# BC127.net
KiCad netlist of a schematic drawn in Altium Designer
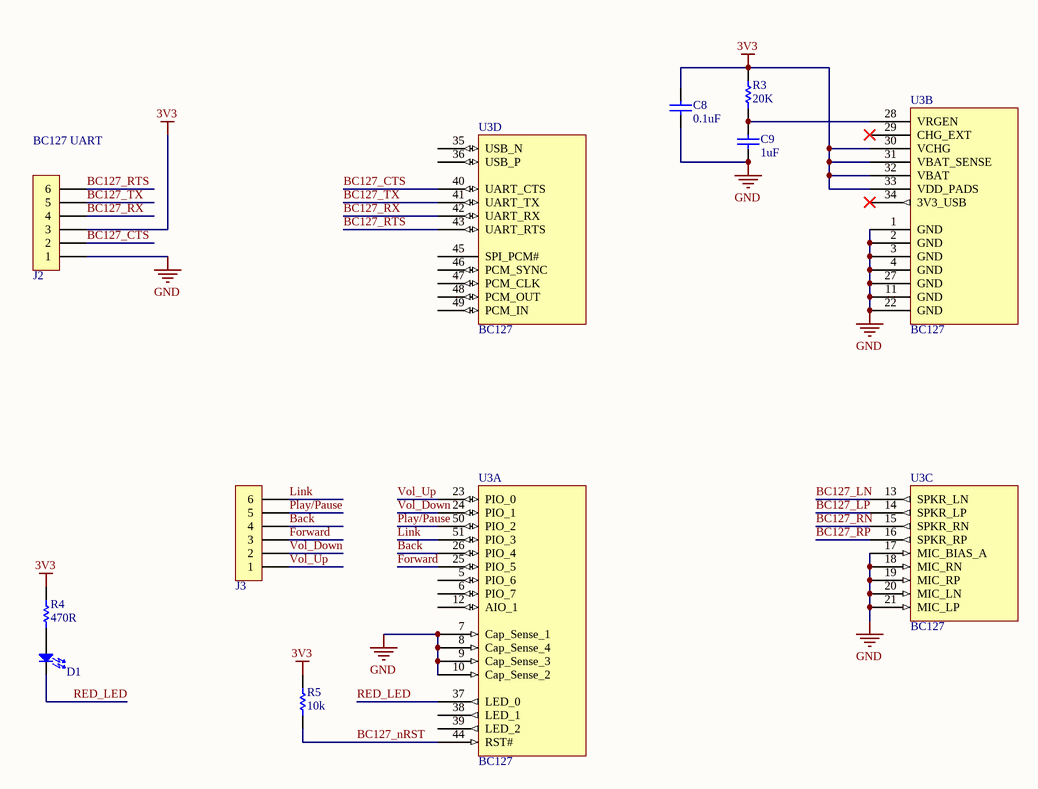
[diagram p0: BC127.SchDoc]

(export (version "E")
  (design (tool "Eeschema 10.0.6"))
  (components
    (comp (ref "C8")
      (value "0.1uF")
      (footprint "CAPC1608X09N")
      (fields
        (field (name "DIGIKEY PART NUMBER") "490-1519-1-ND")
        (field (name "VOLTAGE") "50V")
        (field (name "TOLERANCE") "10%")
      )
      (libsource (lib "Speaker Library") (part "CAP CER 0.1uF 0603"))
    )
    (comp (ref "C9")
      (value "1uF")
      (footprint "CAPC1608X09N")
      (fields
        (field (name "DIGIKEY PART NUMBER") "490-10487-1-ND")
        (field (name "VOLTAGE") "35V")
        (field (name "MANUFACTURER") "Murata")
      )
      (libsource (lib "Speaker Library") (part "CAP CER 1uF 0603"))
    )
    (comp (ref "D1")
      (value "LED 0603")
      (footprint "DIOM1608X08N")
      (fields (field (name "VOLTAGE") "2.2V") (field (name "DIGIKEY PART NUMBER") "160-1447-1-ND"))
      (libsource (lib "Speaker Library") (part "LED 0603"))
    )
    (comp (ref "J2")
      (value "6POS THRU HOLE 2.0MM")
      (footprint "JST PH-6")
      (fields (field (name "DIGIKEY PART NUMBER") "455-1708-ND"))
      (libsource (lib "Speaker Library") (part "6POS THRU HOLE 2.0MM"))
    )
    (comp (ref "J3")
      (value "6POS THRU HOLE 2.0MM")
      (footprint "JST PH-6")
      (fields (field (name "DIGIKEY PART NUMBER") "455-1708-ND"))
      (libsource (lib "Speaker Library") (part "6POS THRU HOLE 2.0MM"))
    )
    (comp (ref "R3")
      (value "20K")
      (footprint "RESC1608X06N")
      (fields
        (field (name "TOLERANCE") "1%")
        (field (name "POWER") "0.1W")
        (field (name "DIGIKEY PART NUMBER") "311-20.0KHRCT-ND")
      )
      (libsource (lib "Speaker Library") (part "RES 20K 0603"))
    )
    (comp (ref "R4")
      (value "470R")
      (footprint "RESC1608X06N")
      (fields
        (field (name "TOLERANCE") "1%")
        (field (name "POWER") "0.25W")
        (field (name "DIGIKEY PART NUMBER") "311-470HRCT-ND")
      )
      (libsource (lib "Speaker Library") (part "RES 470R 0603"))
    )
    (comp (ref "R5")
      (value "10k")
      (footprint "RESC1608X06N")
      (fields
        (field (name "TOLERANCE") "1%")
        (field (name "POWER") "0.1W")
        (field (name "MANUFACTURER") "Yageo")
      )
      (libsource (lib "Speaker Library") (part "RES 10K 0603"))
    )
    (comp (ref "U3") (value "BC127") (footprint "BC127") (libsource (lib "Speaker Library") (part "BC127")))
  )
  (nets
    (net (code "1") (name "/BC127_CTS") (class "Default")
      (node (ref "J2") (pin "2") (pinfunction "2_2") (pintype "passive"))
      (node (ref "U3") (pin "40") (pinfunction "UART_CTS_40") (pintype "bidirectional"))
    )
    (net (code "2") (name "/BC127_LN") (class "Default")
      (node (ref "U3") (pin "13") (pinfunction "SPKR_LN_13") (pintype "output"))
    )
    (net (code "3") (name "/BC127_LP") (class "Default")
      (node (ref "U3") (pin "14") (pinfunction "SPKR_LP_14") (pintype "output"))
    )
    (net (code "4") (name "/BC127_RN") (class "Default")
      (node (ref "U3") (pin "15") (pinfunction "SPKR_RN_15") (pintype "output"))
    )
    (net (code "5") (name "/BC127_RP") (class "Default")
      (node (ref "U3") (pin "16") (pinfunction "SPKR_RP_16") (pintype "output"))
    )
    (net (code "6") (name "/BC127_RTS") (class "Default")
      (node (ref "J2") (pin "6") (pinfunction "6_6") (pintype "passive"))
      (node (ref "U3") (pin "43") (pinfunction "UART_RTS_43") (pintype "bidirectional"))
    )
    (net (code "7") (name "/BC127_RX") (class "Default")
      (node (ref "J2") (pin "4") (pinfunction "4_4") (pintype "passive"))
      (node (ref "U3") (pin "42") (pinfunction "UART_RX_42") (pintype "bidirectional"))
    )
    (net (code "8") (name "/BC127_TX") (class "Default")
      (node (ref "J2") (pin "5") (pinfunction "5_5") (pintype "passive"))
      (node (ref "U3") (pin "41") (pinfunction "UART_TX_41") (pintype "bidirectional"))
    )
    (net (code "9") (name "/BC127_nRST") (class "Default")
      (node (ref "R5") (pin "1") (pinfunction "1_1") (pintype "passive"))
      (node (ref "U3") (pin "44") (pinfunction "RST#_44") (pintype "input"))
    )
    (net (code "10") (name "/Back") (class "Default")
      (node (ref "J3") (pin "4") (pinfunction "4_4") (pintype "passive"))
      (node (ref "U3") (pin "26") (pinfunction "PIO_4_26") (pintype "bidirectional"))
    )
    (net (code "11") (name "/Forward") (class "Default")
      (node (ref "J3") (pin "3") (pinfunction "3_3") (pintype "passive"))
      (node (ref "U3") (pin "25") (pinfunction "PIO_5_25") (pintype "bidirectional"))
    )
    (net (code "12") (name "/Link") (class "Default")
      (node (ref "J3") (pin "6") (pinfunction "6_6") (pintype "passive"))
      (node (ref "U3") (pin "51") (pinfunction "PIO_3_51") (pintype "bidirectional"))
    )
    (net (code "13") (name "/Play{slash}Pause") (class "Default")
      (node (ref "J3") (pin "5") (pinfunction "5_5") (pintype "passive"))
      (node (ref "U3") (pin "50") (pinfunction "PIO_2_50") (pintype "bidirectional"))
    )
    (net (code "14") (name "/RED_LED") (class "Default")
      (node (ref "D1") (pin "1") (pinfunction "K2_1") (pintype "passive"))
      (node (ref "U3") (pin "37") (pinfunction "LED_0_37") (pintype "output"))
    )
    (net (code "15") (name "/Vol_Down") (class "Default")
      (node (ref "J3") (pin "2") (pinfunction "2_2") (pintype "passive"))
      (node (ref "U3") (pin "24") (pinfunction "PIO_1_24") (pintype "bidirectional"))
    )
    (net (code "16") (name "/Vol_Up") (class "Default")
      (node (ref "J3") (pin "1") (pinfunction "1_1") (pintype "passive"))
      (node (ref "U3") (pin "23") (pinfunction "PIO_0_23") (pintype "bidirectional"))
    )
    (net (code "17") (name "3V3") (class "Default")
      (node (ref "C8") (pin "2") (pinfunction "2_2") (pintype "passive"))
      (node (ref "J2") (pin "3") (pinfunction "3_3") (pintype "passive"))
      (node (ref "R3") (pin "2") (pinfunction "2_2") (pintype "passive"))
      (node (ref "R4") (pin "2") (pinfunction "2_2") (pintype "passive"))
      (node (ref "R5") (pin "2") (pinfunction "2_2") (pintype "passive"))
      (node (ref "U3") (pin "30") (pinfunction "VCHG_30") (pintype "passive"))
      (node (ref "U3") (pin "31") (pinfunction "VBAT_SENSE_31") (pintype "passive"))
      (node (ref "U3") (pin "32") (pinfunction "VBAT_32") (pintype "passive"))
      (node (ref "U3") (pin "33") (pinfunction "VDD_PADS_33") (pintype "power_in"))
    )
    (net (code "18") (name "GND") (class "Default")
      (node (ref "C8") (pin "1") (pinfunction "1_1") (pintype "passive"))
      (node (ref "C9") (pin "1") (pinfunction "1_1") (pintype "passive"))
      (node (ref "J2") (pin "1") (pinfunction "1_1") (pintype "passive"))
      (node (ref "U3") (pin "1") (pinfunction "GND_1") (pintype "power_in"))
      (node (ref "U3") (pin "10") (pinfunction "Cap_Sense_2_10") (pintype "input"))
      (node (ref "U3") (pin "11") (pinfunction "GND_11") (pintype "power_in"))
      (node (ref "U3") (pin "17") (pinfunction "MIC_BIAS_A_17") (pintype "input"))
      (node (ref "U3") (pin "18") (pinfunction "MIC_RN_18") (pintype "input"))
      (node (ref "U3") (pin "19") (pinfunction "MIC_RP_19") (pintype "input"))
      (node (ref "U3") (pin "2") (pinfunction "GND_2") (pintype "power_in"))
      (node (ref "U3") (pin "20") (pinfunction "MIC_LN_20") (pintype "input"))
      (node (ref "U3") (pin "21") (pinfunction "MIC_LP_21") (pintype "input"))
      (node (ref "U3") (pin "22") (pinfunction "GND_22") (pintype "power_in"))
      (node (ref "U3") (pin "27") (pinfunction "GND_27") (pintype "power_in"))
      (node (ref "U3") (pin "3") (pinfunction "GND_3") (pintype "power_in"))
      (node (ref "U3") (pin "4") (pinfunction "GND_4") (pintype "power_in"))
      (node (ref "U3") (pin "7") (pinfunction "Cap_Sense_1_7") (pintype "input"))
      (node (ref "U3") (pin "8") (pinfunction "Cap_Sense_4_8") (pintype "input"))
      (node (ref "U3") (pin "9") (pinfunction "Cap_Sense_3_9") (pintype "input"))
    )
    (net (code "19") (name "Net-(D1-A2)") (class "Default")
      (node (ref "D1") (pin "2") (pinfunction "A2_2") (pintype "passive"))
      (node (ref "R4") (pin "1") (pinfunction "1_1") (pintype "passive"))
    )
    (net (code "20") (name "Net-(U3B-VRGEN)") (class "Default")
      (node (ref "C9") (pin "2") (pinfunction "2_2") (pintype "passive"))
      (node (ref "R3") (pin "1") (pinfunction "1_1") (pintype "passive"))
      (node (ref "U3") (pin "28") (pinfunction "VRGEN_28") (pintype "passive"))
    )
    (net (code "21") (name "unconnected-(U3A-AIO_1-Pad12)") (class "Default")
      (node (ref "U3") (pin "12") (pinfunction "AIO_1_12") (pintype "bidirectional"))
    )
    (net (code "22") (name "unconnected-(U3A-LED_1-Pad38)") (class "Default")
      (node (ref "U3") (pin "38") (pinfunction "LED_1_38") (pintype "output"))
    )
    (net (code "23") (name "unconnected-(U3A-LED_2-Pad39)") (class "Default")
      (node (ref "U3") (pin "39") (pinfunction "LED_2_39") (pintype "output"))
    )
    (net (code "24") (name "unconnected-(U3A-PIO_6-Pad5)") (class "Default")
      (node (ref "U3") (pin "5") (pinfunction "PIO_6_5") (pintype "bidirectional"))
    )
    (net (code "25") (name "unconnected-(U3A-PIO_7-Pad6)") (class "Default")
      (node (ref "U3") (pin "6") (pinfunction "PIO_7_6") (pintype "bidirectional"))
    )
    (net (code "26") (name "unconnected-(U3B-3V3_USB-Pad34)") (class "Default")
      (node (ref "U3") (pin "34") (pinfunction "3V3_USB_34") (pintype "output+no_connect"))
    )
    (net (code "27") (name "unconnected-(U3B-CHG_EXT-Pad29)") (class "Default")
      (node (ref "U3") (pin "29") (pinfunction "CHG_EXT_29") (pintype "passive+no_connect"))
    )
    (net (code "28") (name "unconnected-(U3D-PCM_CLK-Pad47)") (class "Default")
      (node (ref "U3") (pin "47") (pinfunction "PCM_CLK_47") (pintype "bidirectional"))
    )
    (net (code "29") (name "unconnected-(U3D-PCM_IN-Pad49)") (class "Default")
      (node (ref "U3") (pin "49") (pinfunction "PCM_IN_49") (pintype "bidirectional"))
    )
    (net (code "30") (name "unconnected-(U3D-PCM_OUT-Pad48)") (class "Default")
      (node (ref "U3") (pin "48") (pinfunction "PCM_OUT_48") (pintype "bidirectional"))
    )
    (net (code "31") (name "unconnected-(U3D-PCM_SYNC-Pad46)") (class "Default")
      (node (ref "U3") (pin "46") (pinfunction "PCM_SYNC_46") (pintype "bidirectional"))
    )
    (net (code "32") (name "unconnected-(U3D-SPI_PCM#-Pad45)") (class "Default")
      (node (ref "U3") (pin "45") (pinfunction "SPI_PCM#_45") (pintype "passive"))
    )
    (net (code "33") (name "unconnected-(U3D-USB_N-Pad35)") (class "Default")
      (node (ref "U3") (pin "35") (pinfunction "USB_N_35") (pintype "bidirectional"))
    )
    (net (code "34") (name "unconnected-(U3D-USB_P-Pad36)") (class "Default")
      (node (ref "U3") (pin "36") (pinfunction "USB_P_36") (pintype "bidirectional"))
    )
  )
)
